# St1x.net
KiCad netlist of a schematic drawn in Altium Designer
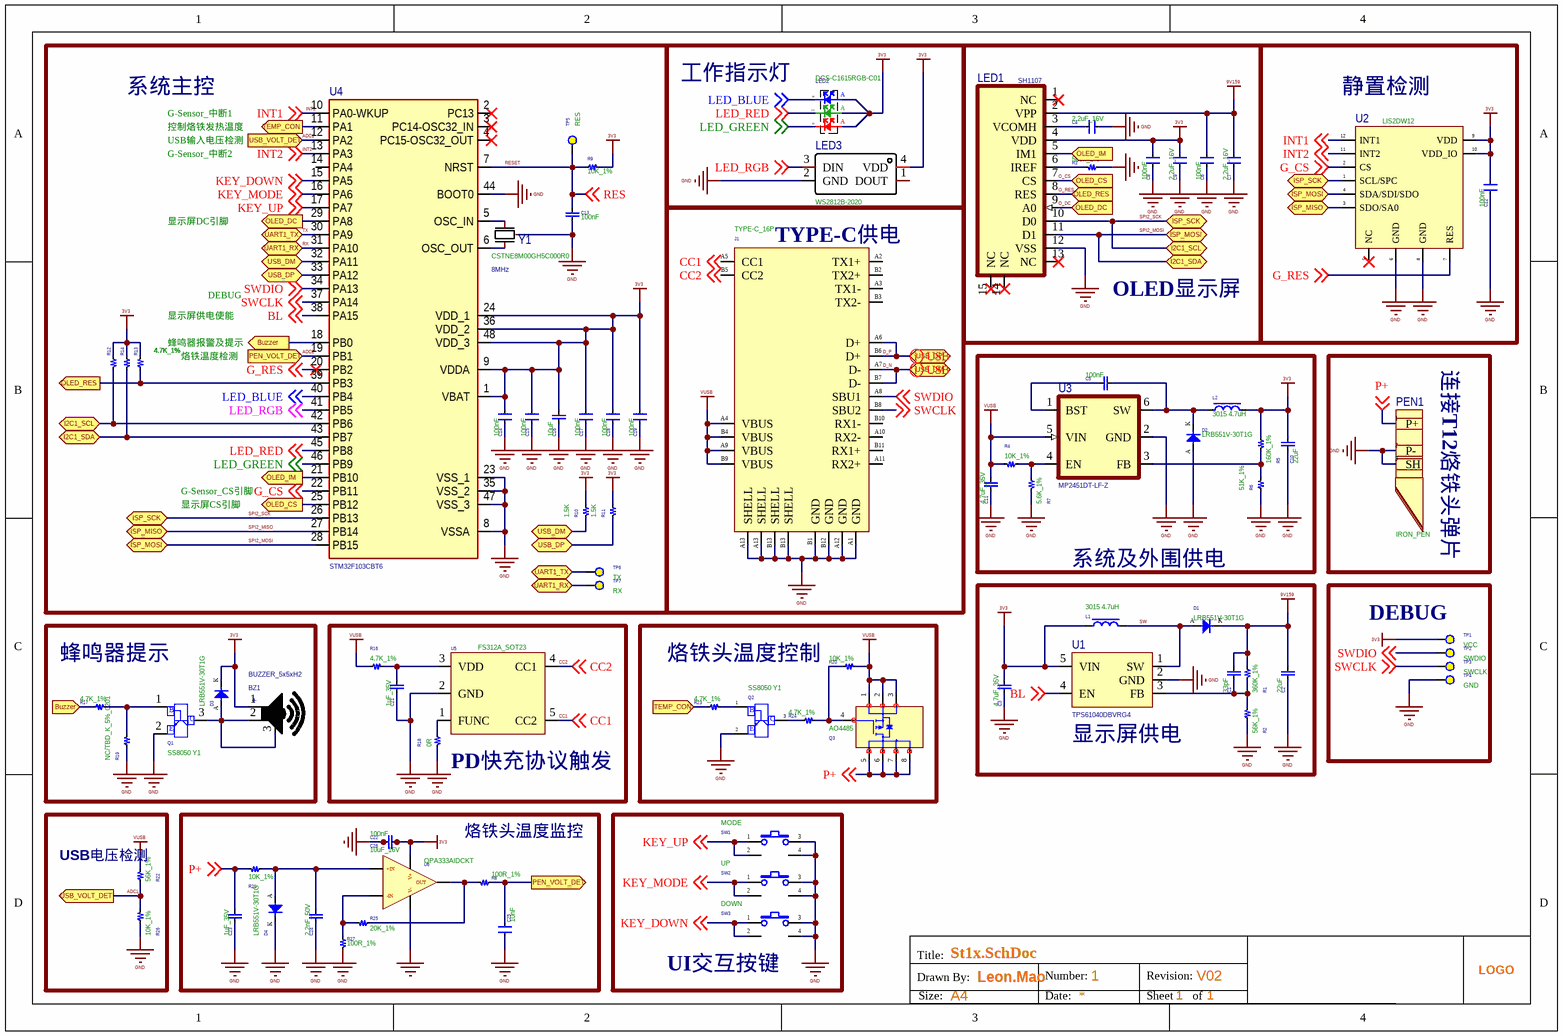
[diagram p0: St1x.SchDoc]

(export (version "E")
  (design (tool "Eeschema 10.0.6"))
  (components
    (comp (ref "BZ1")
      (value "BUZZER_5x5xH2")
      (footprint "BUZ-SMD_GSC5025YA")
      (description "电磁无源蜂鸣器(外部驱动)")
      (libsource (lib "SCHLIB_2022") (part "BZ"))
    )
    (comp (ref "C1")
      (value "33pF")
      (footprint "C1U0402")
      (description "贴片电容")
      (libsource (lib "SCHLIB_2022") (part "CAP_NP"))
    )
    (comp (ref "C2")
      (value "22uF")
      (footprint "CL0603")
      (description "贴片电容")
      (libsource (lib "SCHLIB_2022") (part "CAP_NP"))
    )
    (comp (ref "C3")
      (value "4.7uF_35V")
      (footprint "C4U0402")
      (description "贴片电容")
      (libsource (lib "SCHLIB_2022") (part "CAP_NP"))
    )
    (comp (ref "C4")
      (value "2.2uF_16V")
      (footprint "C4U0402")
      (description "贴片电容")
      (libsource (lib "") (part "CAP_NP_1"))
    )
    (comp (ref "C5")
      (value "100nF")
      (footprint "C1U0402")
      (description "贴片电容")
      (libsource (lib "SCHLIB_2022") (part "CAP_NP"))
    )
    (comp (ref "C6")
      (value "100nF")
      (footprint "C1U0402")
      (description "贴片电容")
      (libsource (lib "") (part "CAP_NP_1"))
    )
    (comp (ref "C7")
      (value "2.2uF_16V")
      (footprint "C4U0402")
      (description "贴片电容")
      (libsource (lib "") (part "CAP_NP_1"))
    )
    (comp (ref "C8")
      (value "100nF")
      (footprint "C1U0402")
      (description "贴片电容")
      (libsource (lib "") (part "CAP_NP_1"))
    )
    (comp (ref "C9")
      (value "2.2uF_16V")
      (footprint "C4U0402")
      (description "贴片电容")
      (libsource (lib "") (part "CAP_NP_1"))
    )
    (comp (ref "C10")
      (value "22uF")
      (footprint "CL0603")
      (description "贴片电容")
      (libsource (lib "SCHLIB_2022") (part "CAP_NP"))
    )
    (comp (ref "C11")
      (value "4.7uF_35V")
      (footprint "C4U0402")
      (description "贴片电容")
      (libsource (lib "SCHLIB_2022") (part "CAP_NP"))
    )
    (comp (ref "C12")
      (value "100nF")
      (footprint "C1U0402")
      (description "贴片电容")
      (libsource (lib "") (part "CAP_NP_1"))
    )
    (comp (ref "C13")
      (value "100nF")
      (footprint "C1U0402")
      (description "贴片电容")
      (libsource (lib "SCHLIB_2022") (part "CAP_NP"))
    )
    (comp (ref "C14")
      (value "100nF")
      (footprint "C1U0402")
      (description "贴片电容")
      (libsource (lib "") (part "CAP_NP_1"))
    )
    (comp (ref "C15")
      (value "100nF")
      (footprint "C1U0402")
      (description "贴片电容")
      (libsource (lib "") (part "CAP_NP_1"))
    )
    (comp (ref "C16")
      (value "10uF")
      (footprint "C4U0402")
      (description "贴片电容")
      (libsource (lib "SCHLIB_2022") (part "CAP_NP"))
    )
    (comp (ref "C17")
      (value "100nF")
      (footprint "C1U0402")
      (description "贴片电容")
      (libsource (lib "") (part "CAP_NP_1"))
    )
    (comp (ref "C18")
      (value "100nF")
      (footprint "C1U0402")
      (description "贴片电容")
      (libsource (lib "") (part "CAP_NP_1"))
    )
    (comp (ref "C19")
      (value "100nF")
      (footprint "C1U0402")
      (description "贴片电容")
      (libsource (lib "") (part "CAP_NP_1"))
    )
    (comp (ref "C21")
      (value "1uF_35V")
      (footprint "C1U0402")
      (description "贴片电容")
      (libsource (lib "SCHLIB_2022") (part "CAP_NP"))
    )
    (comp (ref "C22")
      (value "100nF")
      (footprint "C1U0402")
      (description "贴片电容")
      (libsource (lib "SCHLIB_2022") (part "CAP_NP"))
    )
    (comp (ref "C23")
      (value "1uF_35V")
      (footprint "C1U0402")
      (description "贴片电容")
      (libsource (lib "SCHLIB_2022") (part "CAP_NP"))
    )
    (comp (ref "C24")
      (value "2.2nF_50V")
      (footprint "C4U0402")
      (description "贴片电容")
      (libsource (lib "SCHLIB_2022") (part "CAP_NP"))
    )
    (comp (ref "C25")
      (value "10nF")
      (footprint "C1U0402")
      (description "贴片电容")
      (libsource (lib "") (part "CAP_NP_1"))
    )
    (comp (ref "C26")
      (value "10uF_16V")
      (footprint "C4U0402")
      (description "贴片电容")
      (libsource (lib "SCHLIB_2022") (part "CAP_NP"))
    )
    (comp (ref "D1")
      (value "LRB551V-30T1G")
      (footprint "SOD-323_AK")
      (description "肖特基二极管")
      (libsource (lib "Leon") (part "DIODE"))
    )
    (comp (ref "D2")
      (value "LRB551V-30T1G")
      (footprint "SOD-323_AK")
      (description "肖特基二极管")
      (libsource (lib "Leon") (part "DIODE"))
    )
    (comp (ref "D3")
      (value "LRB551V-30T1G")
      (footprint "SOD-323_AK")
      (description "肖特基二极管")
      (libsource (lib "Leon") (part "DIODE"))
    )
    (comp (ref "D4")
      (value "LRB551V-30T1G")
      (footprint "SOD-323_AK")
      (description "肖特基二极管")
      (libsource (lib "Leon") (part "DIODE"))
    )
    (comp (ref "J1")
      (value "TYPE-C_16P")
      (footprint "TYPE-C_16P")
      (description "TYPE-C母座")
      (libsource (lib "Leon") (part "TYPE-C_RI"))
    )
    (comp (ref "L1")
      (value "3015 4.7uH")
      (footprint "INDC3015")
      (description "功率电感")
      (libsource (lib "") (part "INDUCTOR_2_1"))
    )
    (comp (ref "L2")
      (value "3015 4.7uH")
      (footprint "INDC3015")
      (description "功率电感")
      (libsource (lib "SCHLIB_2022") (part "INDUCTOR_2"))
    )
    (comp (ref "LED1")
      (value "SH1107")
      (footprint "CON_13P_0.7mm-FPC")
      (description "QG-2880TSWKG01")
      (fields
        (field (name "MF") "{'manufacturer': u'Texas Instruments'}")
        (field (name "MP") "LP2985AIM5-5.0")
      )
      (libsource (lib "SCHLIB_2022") (part "SH1107"))
    )
    (comp (ref "LED2")
      (value "DCS-C1615RGB-C01")
      (footprint "RGB_DCS-C1615RGB-C01")
      (description "红绿蓝三色发光二极管")
      (libsource (lib "Leon") (part "LED_RGBS"))
    )
    (comp (ref "LED3")
      (value "WS2812B-2020")
      (footprint "LED_2020")
      (fields (field (name "MANUFACTURER PART") "Yo-WS2812B-3528反贴雾状"))
      (libsource (lib "altium-import") (part "root_0_mirrored_YO-WS2812B-3528反贴_"))
    )
    (comp (ref "PEN1") (value "IRON_PEN") (footprint "T13") (libsource (lib "SCHLIB_2022") (part "IRON_PEN")))
    (comp (ref "Q1")
      (value "SS8050 Y1")
      (footprint "SOT-23_123")
      (description "NPN三极管")
      (libsource (lib "PCBDEV_Library") (part "NPN"))
    )
    (comp (ref "Q2")
      (value "SS8050 Y1")
      (footprint "SOT-23_123")
      (description "NPN三极管")
      (libsource (lib "SCHLIB_2022") (part "NPN"))
    )
    (comp (ref "Q3")
      (value "AO4485")
      (footprint "SO-8M")
      (description "P沟道 40V 10A")
      (libsource (lib "SCHLIB_2022") (part "AO4485"))
    )
    (comp (ref "R1")
      (value "360K_1%")
      (footprint "RN0402")
      (description "贴片电阻")
      (libsource (lib "Leon") (part "ResSemi_3"))
    )
    (comp (ref "R2")
      (value "56K_1%")
      (footprint "RN0402")
      (description "贴片电阻")
      (libsource (lib "Leon") (part "ResSemi_3"))
    )
    (comp (ref "R3")
      (value "560k_1%")
      (footprint "RN0402")
      (description "贴片电阻")
      (libsource (lib "Leon") (part "ResSemi_3"))
    )
    (comp (ref "R4")
      (value "10K_1%")
      (footprint "RN0402")
      (description "贴片电阻")
      (libsource (lib "Leon") (part "ResSemi_3"))
    )
    (comp (ref "R5")
      (value "160K_1%")
      (footprint "RN0402")
      (description "贴片电阻")
      (libsource (lib "Leon") (part "ResSemi_3"))
    )
    (comp (ref "R6")
      (value "51K_1%")
      (footprint "RN0402")
      (description "贴片电阻")
      (libsource (lib "Leon") (part "ResSemi_3"))
    )
    (comp (ref "R7")
      (value "5.6K_1%")
      (footprint "RN0402")
      (description "贴片电阻")
      (libsource (lib "Leon") (part "ResSemi_3"))
    )
    (comp (ref "R8")
      (value "100R_1%")
      (footprint "RN0402")
      (description "贴片电阻")
      (libsource (lib "Leon") (part "ResSemi_3"))
    )
    (comp (ref "R9")
      (value "10K_1%")
      (footprint "RN0402")
      (description "贴片电阻")
      (libsource (lib "Leon") (part "ResSemi_3"))
    )
    (comp (ref "R10")
      (value "1.5K")
      (footprint "RN0402")
      (description "贴片电阻")
      (libsource (lib "Leon") (part "ResSemi_3"))
    )
    (comp (ref "R11")
      (value "1.5K")
      (footprint "RN0402")
      (description "贴片电阻")
      (libsource (lib "Leon") (part "ResSemi_3"))
    )
    (comp (ref "R12")
      (value "4.7K_1%")
      (footprint "RN0402")
      (description "贴片电阻")
      (libsource (lib "Leon") (part "ResSemi_3"))
    )
    (comp (ref "R13")
      (value "4.7K_1%")
      (footprint "RN0402")
      (description "贴片电阻")
      (libsource (lib "Leon") (part "ResSemi_3"))
    )
    (comp (ref "R14")
      (value "4.7K_1%")
      (footprint "RN0402")
      (description "贴片电阻")
      (libsource (lib "Leon") (part "ResSemi_3"))
    )
    (comp (ref "R16")
      (value "4.7K_1%")
      (footprint "RN0402")
      (description "贴片电阻")
      (libsource (lib "Leon") (part "ResSemi_3"))
    )
    (comp (ref "R17")
      (value "4.7K_1%")
      (footprint "RN0402")
      (description "贴片电阻")
      (libsource (lib "Leon") (part "ResSemi_3"))
    )
    (comp (ref "R18")
      (value "0R")
      (footprint "RN0402")
      (description "贴片电阻")
      (libsource (lib "Leon") (part "ResSemi_3"))
    )
    (comp (ref "R19")
      (value "NC/TBD_K_5%_0201")
      (footprint "RN0402")
      (description "贴片电阻")
      (libsource (lib "Leon") (part "ResSemi_3"))
    )
    (comp (ref "R20")
      (value "10K_1%")
      (footprint "RN0402")
      (description "贴片电阻")
      (libsource (lib "Leon") (part "ResSemi_3"))
    )
    (comp (ref "R21")
      (value "10K_1%")
      (footprint "RN0603")
      (description "贴片电阻")
      (libsource (lib "Leon") (part "ResSemi_3"))
    )
    (comp (ref "R22")
      (value "56K_1%")
      (footprint "RN0402")
      (description "贴片电阻")
      (libsource (lib "Leon") (part "ResSemi_3"))
    )
    (comp (ref "R23")
      (value "4.7K_1%")
      (footprint "RN0402")
      (description "贴片电阻")
      (libsource (lib "Leon") (part "ResSemi_3"))
    )
    (comp (ref "R24")
      (value "4.7K_1%")
      (footprint "RN0402")
      (description "贴片电阻")
      (libsource (lib "Leon") (part "ResSemi_3"))
    )
    (comp (ref "R25")
      (value "20K_1%")
      (footprint "RN0402")
      (description "贴片电阻")
      (libsource (lib "Leon") (part "ResSemi_3"))
    )
    (comp (ref "R26")
      (value "10K_1%")
      (footprint "RN0402")
      (description "贴片电阻")
      (libsource (lib "Leon") (part "ResSemi_3"))
    )
    (comp (ref "R27")
      (value "100R_1%")
      (footprint "RN0402")
      (description "贴片电阻")
      (libsource (lib "Leon") (part "ResSemi_3"))
    )
    (comp (ref "SW1")
      (value "MODE")
      (footprint "KEY-SMD_4P-L4.2-W3.2-P2.20-LS5.1-TL")
      (description "轻触开关")
      (libsource (lib "SCHLIB_2022") (part "SW PUSHBUTTON"))
    )
    (comp (ref "SW2")
      (value "UP")
      (footprint "KEY-SMD_4P-L4.2-W3.2-P2.20-LS5.1-TL")
      (description "轻触开关")
      (libsource (lib "SCHLIB_2022") (part "SW PUSHBUTTON"))
    )
    (comp (ref "SW3")
      (value "DOWN")
      (footprint "KEY-SMD_4P-L4.2-W3.2-P2.20-LS5.1-TL")
      (description "轻触开关")
      (libsource (lib "SCHLIB_2022") (part "SW PUSHBUTTON"))
    )
    (comp (ref "TP1") (value "VCC") (footprint "SMD0808") (libsource (lib "SCHLIB_2022") (part "TEST")))
    (comp (ref "TP2") (value "SWDIO") (footprint "SMD0808") (libsource (lib "SCHLIB_2022") (part "TEST")))
    (comp (ref "TP3") (value "SWCLK") (footprint "SMD0808") (libsource (lib "SCHLIB_2022") (part "TEST")))
    (comp (ref "TP4") (value "GND") (footprint "SMD0808") (libsource (lib "SCHLIB_2022") (part "TEST")))
    (comp (ref "TP5") (value "RES") (footprint "SMD0808") (libsource (lib "SCHLIB_2022") (part "TEST")))
    (comp (ref "TP6") (value "TX") (footprint "SMD0808") (libsource (lib "SCHLIB_2022") (part "TEST")))
    (comp (ref "TP7") (value "RX") (footprint "SMD0808") (libsource (lib "SCHLIB_2022") (part "TEST")))
    (comp (ref "U1")
      (value "TPS61040DBVRG4")
      (footprint "SOT23-5")
      (description "DC-DC芯片")
      (libsource (lib "SCHLIB_2022") (part "TPS61040DBVRG4_[C7722]"))
    )
    (comp (ref "U2")
      (value "LIS2DW12")
      (footprint "LGA12_20x20x07")
      (libsource (lib "SCHLIB_2022") (part "LIS2DW12"))
    )
    (comp (ref "U3")
      (value "MP2451DT-LF-Z")
      (footprint "SOT23-6")
      (fields
        (field (name "MF") "{'manufacturer': u'Texas Instruments'}")
        (field (name "MP") "LP2985AIM5-5.0")
      )
      (libsource (lib "SCHLIB_2022") (part "MP2451DT-LF-Z"))
    )
    (comp (ref "U4")
      (value "STM32F103CBT6")
      (footprint "LQFP48-7x7mm")
      (description "No Description Available")
      (fields (field (name "COPYRIGHT") "Copyright (C) 2023 Ultra Librarian. All rights reserved."))
      (libsource (lib "SCHLIB_2022") (part "STM32F103CBT6"))
    )
    (comp (ref "U5")
      (value "FS312A_SOT23")
      (footprint "SOT23-5")
      (description "USB Type-C PD快充协议智能触发芯片")
      (libsource (lib "SCHLIB_2022") (part "FS312A"))
    )
    (comp (ref "U6")
      (value "OPA333AIDCKT")
      (footprint "SOT23-5")
      (libsource (lib "SCHLIB_2022") (part "OPA333_SOT23"))
    )
    (comp (ref "Y1")
      (value "CSTNE8M00GH5C000R0")
      (footprint "OSC-SMD_3P-L3.2-W1.3-P1.20-L")
      (description "频率:8MHz;频率容差:±0.07%;内藏负载电容:33pF;谐振阻抗:40Ω;")
      (fields (field (name "MANUFACTURER") "muRata(村田)") (field (name "ALTIUM_VALUE") "8MHz"))
      (libsource (lib "SCHLIB_2022") (part "CSTNE8M00GH5C000R0"))
    )
  )
  (nets
    (net (code "1") (name "/ADC1") (class "Default")
      (node (ref "R22") (pin "1") (pinfunction "1_1") (pintype "passive"))
      (node (ref "R26") (pin "2") (pinfunction "2_2") (pintype "passive"))
      (node (ref "U4") (pin "12") (pinfunction "PA2_12") (pintype "passive"))
    )
    (net (code "2") (name "/ADC2") (class "Default")
      (node (ref "C25") (pin "1") (pinfunction "1_1") (pintype "passive"))
      (node (ref "R8") (pin "1") (pinfunction "1_1") (pintype "passive"))
      (node (ref "U4") (pin "19") (pinfunction "PB1_19") (pintype "passive"))
    )
    (net (code "3") (name "/Buzzer") (class "Default")
      (node (ref "R17") (pin "1") (pinfunction "1_1") (pintype "passive"))
      (node (ref "U4") (pin "18") (pinfunction "PB0_18") (pintype "passive"))
    )
    (net (code "4") (name "/D_N") (class "Default")
      (node (ref "J1") (pin "A7") (pinfunction "D-_A7") (pintype "passive"))
      (node (ref "J1") (pin "B7") (pinfunction "D-_B7") (pintype "passive"))
      (node (ref "R10") (pin "2") (pinfunction "2_2") (pintype "passive"))
      (node (ref "U4") (pin "32") (pinfunction "PA11_32") (pintype "passive"))
    )
    (net (code "5") (name "/D_P") (class "Default")
      (node (ref "J1") (pin "A6") (pinfunction "D+_A6") (pintype "passive"))
      (node (ref "J1") (pin "B6") (pinfunction "D+_B6") (pintype "passive"))
      (node (ref "R11") (pin "2") (pinfunction "2_2") (pintype "passive"))
      (node (ref "U4") (pin "33") (pinfunction "PA12_33") (pintype "passive"))
    )
    (net (code "6") (name "/OLED_IM") (class "Default")
      (node (ref "LED1") (pin "5") (pinfunction "IM1_5") (pintype "passive"))
      (node (ref "U4") (pin "21") (pinfunction "PB10_21") (pintype "passive"))
    )
    (net (code "7") (name "/O_CS") (class "Default")
      (node (ref "LED1") (pin "7") (pinfunction "CS_7") (pintype "passive"))
      (node (ref "U4") (pin "25") (pinfunction "PB12_25") (pintype "passive"))
    )
    (net (code "8") (name "/O_DC") (class "Default")
      (node (ref "LED1") (pin "9") (pinfunction "A0_9") (pintype "input"))
      (node (ref "U4") (pin "29") (pinfunction "PA8_29") (pintype "passive"))
    )
    (net (code "9") (name "/O_RES") (class "Default")
      (node (ref "LED1") (pin "8") (pinfunction "RES_8") (pintype "passive"))
      (node (ref "R13") (pin "2") (pinfunction "2_2") (pintype "passive"))
      (node (ref "U4") (pin "39") (pinfunction "PB3_39") (pintype "passive"))
    )
    (net (code "10") (name "/RX") (class "Default")
      (node (ref "TP7") (pin "1") (pinfunction "1_1") (pintype "passive"))
      (node (ref "U4") (pin "31") (pinfunction "PA10_31") (pintype "passive"))
    )
    (net (code "11") (name "/SPI2_MISO") (class "Default")
      (node (ref "U2") (pin "3") (pinfunction "SDO/SA0_3") (pintype "passive"))
      (node (ref "U4") (pin "27") (pinfunction "PB14_27") (pintype "passive"))
    )
    (net (code "12") (name "/SPI2_MOSI") (class "Default")
      (node (ref "LED1") (pin "11") (pinfunction "D1_11") (pintype "passive"))
      (node (ref "R14") (pin "1") (pinfunction "1_1") (pintype "passive"))
      (node (ref "U2") (pin "4") (pinfunction "SDA/SDI/SDO_4") (pintype "passive"))
      (node (ref "U4") (pin "28") (pinfunction "PB15_28") (pintype "passive"))
      (node (ref "U4") (pin "43") (pinfunction "PB7_43") (pintype "passive"))
    )
    (net (code "13") (name "/SPI2_SCK") (class "Default")
      (node (ref "LED1") (pin "10") (pinfunction "D0_10") (pintype "passive"))
      (node (ref "R12") (pin "1") (pinfunction "1_1") (pintype "passive"))
      (node (ref "U2") (pin "1") (pinfunction "SCL/SPC_1") (pintype "passive"))
      (node (ref "U4") (pin "26") (pinfunction "PB13_26") (pintype "passive"))
      (node (ref "U4") (pin "42") (pinfunction "PB6_42") (pintype "passive"))
    )
    (net (code "14") (name "/SW") (class "Default")
      (node (ref "D1") (pin "A") (pinfunction "ANODE_A") (pintype "passive"))
      (node (ref "L1") (pin "2") (pinfunction "2_2") (pintype "passive"))
      (node (ref "U1") (pin "1") (pinfunction "SW_1") (pintype "passive"))
    )
    (net (code "15") (name "/TEMP_CON") (class "Default")
      (node (ref "R23") (pin "1") (pinfunction "1_1") (pintype "passive"))
      (node (ref "U4") (pin "11") (pinfunction "PA1_11") (pintype "passive"))
    )
    (net (code "16") (name "/TX") (class "Default")
      (node (ref "TP6") (pin "1") (pinfunction "1_1") (pintype "passive"))
      (node (ref "U4") (pin "30") (pinfunction "PA9_30") (pintype "passive"))
    )
    (net (code "17") (name "3V3") (class "Default")
      (node (ref "BZ1") (pin "1") (pinfunction "+_1") (pintype "passive"))
      (node (ref "C10") (pin "2") (pinfunction "2_2") (pintype "passive"))
      (node (ref "C12") (pin "1") (pinfunction "1_1") (pintype "passive"))
      (node (ref "C14") (pin "1") (pinfunction "1_1") (pintype "passive"))
      (node (ref "C15") (pin "1") (pinfunction "1_1") (pintype "passive"))
      (node (ref "C16") (pin "2") (pinfunction "2_2") (pintype "passive"))
      (node (ref "C17") (pin "1") (pinfunction "1_1") (pintype "passive"))
      (node (ref "C18") (pin "1") (pinfunction "1_1") (pintype "passive"))
      (node (ref "C19") (pin "1") (pinfunction "1_1") (pintype "passive"))
      (node (ref "C22") (pin "2") (pinfunction "2_2") (pintype "passive"))
      (node (ref "C26") (pin "1") (pinfunction "1_1") (pintype "passive"))
      (node (ref "C3") (pin "2") (pinfunction "2_2") (pintype "passive"))
      (node (ref "C8") (pin "1") (pinfunction "1_1") (pintype "passive"))
      (node (ref "C9") (pin "1") (pinfunction "1_1") (pintype "passive"))
      (node (ref "D3") (pin "K") (pinfunction "CATHODE_K") (pintype "passive"))
      (node (ref "L1") (pin "1") (pinfunction "1_1") (pintype "passive"))
      (node (ref "L2") (pin "1") (pinfunction "1_1") (pintype "passive"))
      (node (ref "LED1") (pin "4") (pinfunction "VDD_4") (pintype "power_in"))
      (node (ref "LED2") (pin "A") (pinfunction "A_A") (pintype "passive"))
      (node (ref "LED3") (pin "4") (pinfunction "VDD_4") (pintype "passive"))
      (node (ref "R10") (pin "1") (pinfunction "1_1") (pintype "passive"))
      (node (ref "R11") (pin "1") (pinfunction "1_1") (pintype "passive"))
      (node (ref "R12") (pin "2") (pinfunction "2_2") (pintype "passive"))
      (node (ref "R13") (pin "1") (pinfunction "1_1") (pintype "passive"))
      (node (ref "R14") (pin "2") (pinfunction "2_2") (pintype "passive"))
      (node (ref "R5") (pin "1") (pinfunction "1_1") (pintype "passive"))
      (node (ref "R9") (pin "1") (pinfunction "1_1") (pintype "passive"))
      (node (ref "TP1") (pin "1") (pinfunction "1_1") (pintype "passive"))
      (node (ref "U1") (pin "5") (pinfunction "VIN_5") (pintype "passive"))
      (node (ref "U2") (pin "10") (pinfunction "VDD_IO_10") (pintype "passive"))
      (node (ref "U2") (pin "9") (pinfunction "VDD_9") (pintype "passive"))
      (node (ref "U4") (pin "1") (pinfunction "VBAT_1") (pintype "power_in"))
      (node (ref "U4") (pin "24") (pinfunction "VDD_1_24") (pintype "power_in"))
      (node (ref "U4") (pin "36") (pinfunction "VDD_2_36") (pintype "power_in"))
      (node (ref "U4") (pin "48") (pinfunction "VDD_3_48") (pintype "power_in"))
      (node (ref "U4") (pin "9") (pinfunction "VDDA_9") (pintype "power_in"))
      (node (ref "U6") (pin "5") (pinfunction "V+_5") (pintype "passive"))
    )
    (net (code "18") (name "9V159") (class "Default")
      (node (ref "C1") (pin "2") (pinfunction "2_2") (pintype "passive"))
      (node (ref "C2") (pin "2") (pinfunction "2_2") (pintype "passive"))
      (node (ref "C6") (pin "1") (pinfunction "1_1") (pintype "passive"))
      (node (ref "C7") (pin "1") (pinfunction "1_1") (pintype "passive"))
      (node (ref "D1") (pin "K") (pinfunction "CATHODE_K") (pintype "passive"))
      (node (ref "LED1") (pin "2") (pinfunction "VPP_2") (pintype "power_in"))
      (node (ref "R1") (pin "1") (pinfunction "1_1") (pintype "passive"))
    )
    (net (code "19") (name "BL") (class "Default")
      (node (ref "U1") (pin "4") (pinfunction "EN_4") (pintype "passive"))
      (node (ref "U4") (pin "38") (pinfunction "PA15_38") (pintype "passive"))
    )
    (net (code "20") (name "CC1") (class "Default")
      (node (ref "J1") (pin "A5") (pinfunction "CC1_A5") (pintype "passive"))
      (node (ref "U5") (pin "5") (pinfunction "CC2_5") (pintype "passive"))
    )
    (net (code "21") (name "CC2") (class "Default")
      (node (ref "J1") (pin "B5") (pinfunction "CC2_B5") (pintype "passive"))
      (node (ref "U5") (pin "4") (pinfunction "CC1_4") (pintype "passive"))
    )
    (net (code "22") (name "GND") (class "Default")
      (node (ref "C10") (pin "1") (pinfunction "1_1") (pintype "passive"))
      (node (ref "C11") (pin "1") (pinfunction "1_1") (pintype "passive"))
      (node (ref "C12") (pin "2") (pinfunction "2_2") (pintype "passive"))
      (node (ref "C13") (pin "2") (pinfunction "2_2") (pintype "passive"))
      (node (ref "C14") (pin "2") (pinfunction "2_2") (pintype "passive"))
      (node (ref "C15") (pin "2") (pinfunction "2_2") (pintype "passive"))
      (node (ref "C16") (pin "1") (pinfunction "1_1") (pintype "passive"))
      (node (ref "C17") (pin "2") (pinfunction "2_2") (pintype "passive"))
      (node (ref "C18") (pin "2") (pinfunction "2_2") (pintype "passive"))
      (node (ref "C19") (pin "2") (pinfunction "2_2") (pintype "passive"))
      (node (ref "C2") (pin "1") (pinfunction "1_1") (pintype "passive"))
      (node (ref "C21") (pin "1") (pinfunction "1_1") (pintype "passive"))
      (node (ref "C22") (pin "1") (pinfunction "1_1") (pintype "passive"))
      (node (ref "C23") (pin "2") (pinfunction "2_2") (pintype "passive"))
      (node (ref "C24") (pin "2") (pinfunction "2_2") (pintype "passive"))
      (node (ref "C25") (pin "2") (pinfunction "2_2") (pintype "passive"))
      (node (ref "C26") (pin "2") (pinfunction "2_2") (pintype "passive"))
      (node (ref "C3") (pin "1") (pinfunction "1_1") (pintype "passive"))
      (node (ref "C4") (pin "2") (pinfunction "2_2") (pintype "passive"))
      (node (ref "C6") (pin "2") (pinfunction "2_2") (pintype "passive"))
      (node (ref "C7") (pin "2") (pinfunction "2_2") (pintype "passive"))
      (node (ref "C8") (pin "2") (pinfunction "2_2") (pintype "passive"))
      (node (ref "C9") (pin "2") (pinfunction "2_2") (pintype "passive"))
      (node (ref "D2") (pin "A") (pinfunction "ANODE_A") (pintype "passive"))
      (node (ref "D4") (pin "K") (pinfunction "CATHODE_K") (pintype "passive"))
      (node (ref "J1") (pin "A1") (pinfunction "GND_A1") (pintype "passive"))
      (node (ref "J1") (pin "A12") (pinfunction "GND_A12") (pintype "passive"))
      (node (ref "J1") (pin "A13") (pinfunction "SHELL_A13") (pintype "passive"))
      (node (ref "J1") (pin "B1") (pinfunction "GND_B1") (pintype "passive"))
      (node (ref "J1") (pin "B12") (pinfunction "GND_B12") (pintype "passive"))
      (node (ref "J1") (pin "B13") (pinfunction "SHELL_B13") (pintype "passive"))
      (node (ref "LED1") (pin "12") (pinfunction "VSS_12") (pintype "passive"))
      (node (ref "LED3") (pin "2") (pinfunction "GND_2") (pintype "passive"))
      (node (ref "PEN1") (pin "2") (pinfunction "P-_2") (pintype "passive"))
      (node (ref "PEN1") (pin "3") (pinfunction "SH_3") (pintype "passive"))
      (node (ref "Q1") (pin "2") (pinfunction "EMITTER_2") (pintype "passive"))
      (node (ref "Q2") (pin "2") (pinfunction "EMITTER_2") (pintype "passive"))
      (node (ref "R18") (pin "2") (pinfunction "2_2") (pintype "passive"))
      (node (ref "R19") (pin "1") (pinfunction "1_1") (pintype "passive"))
      (node (ref "R2") (pin "1") (pinfunction "1_1") (pintype "passive"))
      (node (ref "R26") (pin "1") (pinfunction "1_1") (pintype "passive"))
      (node (ref "R27") (pin "2") (pinfunction "2_2") (pintype "passive"))
      (node (ref "R3") (pin "1") (pinfunction "1_1") (pintype "passive"))
      (node (ref "R6") (pin "1") (pinfunction "1_1") (pintype "passive"))
      (node (ref "R7") (pin "2") (pinfunction "2_2") (pintype "passive"))
      (node (ref "SW1") (pin "3") (pinfunction "3_3") (pintype "passive"))
      (node (ref "SW1") (pin "4") (pinfunction "4_4") (pintype "passive"))
      (node (ref "SW2") (pin "3") (pinfunction "3_3") (pintype "passive"))
      (node (ref "SW2") (pin "4") (pinfunction "4_4") (pintype "passive"))
      (node (ref "SW3") (pin "3") (pinfunction "3_3") (pintype "passive"))
      (node (ref "SW3") (pin "4") (pinfunction "4_4") (pintype "passive"))
      (node (ref "TP4") (pin "1") (pinfunction "1_1") (pintype "passive"))
      (node (ref "U1") (pin "2") (pinfunction "GND_2") (pintype "passive"))
      (node (ref "U2") (pin "6") (pinfunction "GND_6") (pintype "passive"))
      (node (ref "U2") (pin "8") (pinfunction "GND_8") (pintype "passive"))
      (node (ref "U3") (pin "2") (pinfunction "GND_2") (pintype "power_in"))
      (node (ref "U4") (pin "23") (pinfunction "VSS_1_23") (pintype "power_in"))
      (node (ref "U4") (pin "35") (pinfunction "VSS_2_35") (pintype "power_in"))
      (node (ref "U4") (pin "44") (pinfunction "BOOT0_44") (pintype "passive"))
      (node (ref "U4") (pin "47") (pinfunction "VSS_3_47") (pintype "power_in"))
      (node (ref "U4") (pin "8") (pinfunction "VSSA_8") (pintype "power_in"))
      (node (ref "U5") (pin "2") (pinfunction "GND_2") (pintype "passive"))
      (node (ref "U6") (pin "2") (pinfunction "V-_2") (pintype "passive"))
      (node (ref "Y1") (pin "2") (pinfunction "GND_2") (pintype "passive"))
    )
    (net (code "23") (name "G_CS") (class "Default")
      (node (ref "U2") (pin "2") (pinfunction "CS_2") (pintype "passive"))
      (node (ref "U4") (pin "22") (pinfunction "PB11_22") (pintype "passive"))
    )
    (net (code "24") (name "G_RES") (class "Default")
      (node (ref "U2") (pin "7") (pinfunction "RES_7") (pintype "passive"))
      (node (ref "U4") (pin "20") (pinfunction "PB2_20") (pintype "passive"))
    )
    (net (code "25") (name "INT1") (class "Default")
      (node (ref "U2") (pin "12") (pinfunction "INT1_12") (pintype "passive"))
      (node (ref "U4") (pin "10") (pinfunction "PA0-WKUP_10") (pintype "passive"))
    )
    (net (code "26") (name "INT2") (class "Default")
      (node (ref "U2") (pin "11") (pinfunction "INT2_11") (pintype "passive"))
      (node (ref "U4") (pin "13") (pinfunction "PA3_13") (pintype "passive"))
    )
    (net (code "27") (name "KEY_DOWN") (class "Default")
      (node (ref "SW3") (pin "1") (pinfunction "1_1") (pintype "passive"))
      (node (ref "SW3") (pin "2") (pinfunction "2_2") (pintype "passive"))
      (node (ref "U4") (pin "15") (pinfunction "PA5_15") (pintype "passive"))
    )
    (net (code "28") (name "KEY_MODE") (class "Default")
      (node (ref "SW2") (pin "1") (pinfunction "1_1") (pintype "passive"))
      (node (ref "SW2") (pin "2") (pinfunction "2_2") (pintype "passive"))
      (node (ref "U4") (pin "16") (pinfunction "PA6_16") (pintype "passive"))
    )
    (net (code "29") (name "KEY_UP") (class "Default")
      (node (ref "SW1") (pin "1") (pinfunction "1_1") (pintype "passive"))
      (node (ref "SW1") (pin "2") (pinfunction "2_2") (pintype "passive"))
      (node (ref "U4") (pin "17") (pinfunction "PA7_17") (pintype "passive"))
    )
    (net (code "30") (name "LED_BLUE") (class "Default")
      (node (ref "LED2") (pin "BC") (pinfunction "BC_BC") (pintype "passive"))
      (node (ref "U4") (pin "40") (pinfunction "PB4_40") (pintype "passive"))
    )
    (net (code "31") (name "LED_GREEN") (class "Default")
      (node (ref "LED2") (pin "RC") (pinfunction "RC_RC") (pintype "passive"))
      (node (ref "U4") (pin "46") (pinfunction "PB9_46") (pintype "passive"))
    )
    (net (code "32") (name "LED_RED") (class "Default")
      (node (ref "LED2") (pin "GC") (pinfunction "GC_GC") (pintype "passive"))
      (node (ref "U4") (pin "45") (pinfunction "PB8_45") (pintype "passive"))
    )
    (net (code "33") (name "LED_RGB") (class "Default")
      (node (ref "LED3") (pin "3") (pinfunction "DIN_3") (pintype "passive"))
      (node (ref "U4") (pin "41") (pinfunction "PB5_41") (pintype "passive"))
    )
    (net (code "34") (name "Net-(D2-CATHODE)") (class "Default")
      (node (ref "C5") (pin "1") (pinfunction "1_1") (pintype "passive"))
      (node (ref "D2") (pin "K") (pinfunction "CATHODE_K") (pintype "passive"))
      (node (ref "L2") (pin "2") (pinfunction "2_2") (pintype "passive"))
      (node (ref "U3") (pin "6") (pinfunction "SW_6") (pintype "passive"))
    )
    (net (code "35") (name "Net-(D3-ANODE)") (class "Default")
      (node (ref "BZ1") (pin "2") (pinfunction "-_2") (pintype "passive"))
      (node (ref "BZ1") (pin "3") (pinfunction "-_3") (pintype "passive"))
      (node (ref "D3") (pin "A") (pinfunction "ANODE_A") (pintype "passive"))
      (node (ref "Q1") (pin "3") (pinfunction "COLLECTOR_3") (pintype "passive"))
    )
    (net (code "36") (name "Net-(D4-ANODE)") (class "Default")
      (node (ref "C24") (pin "1") (pinfunction "1_1") (pintype "passive"))
      (node (ref "D4") (pin "A") (pinfunction "ANODE_A") (pintype "passive"))
      (node (ref "R21") (pin "1") (pinfunction "1_1") (pintype "passive"))
      (node (ref "U6") (pin "3") (pinfunction "+IN_3") (pintype "passive"))
    )
    (net (code "37") (name "Net-(LED1-IREF)") (class "Default")
      (node (ref "LED1") (pin "6") (pinfunction "IREF_6") (pintype "passive"))
      (node (ref "R3") (pin "2") (pinfunction "2_2") (pintype "passive"))
    )
    (net (code "38") (name "Net-(LED1-VCOMH)") (class "Default")
      (node (ref "C4") (pin "1") (pinfunction "1_1") (pintype "passive"))
      (node (ref "LED1") (pin "3") (pinfunction "VCOMH_3") (pintype "passive"))
    )
    (net (code "39") (name "Net-(Q1-BASE)") (class "Default")
      (node (ref "Q1") (pin "1") (pinfunction "BASE_1") (pintype "passive"))
      (node (ref "R17") (pin "2") (pinfunction "2_2") (pintype "passive"))
      (node (ref "R19") (pin "2") (pinfunction "2_2") (pintype "passive"))
    )
    (net (code "40") (name "Net-(Q2-BASE)") (class "Default")
      (node (ref "Q2") (pin "1") (pinfunction "BASE_1") (pintype "passive"))
      (node (ref "R23") (pin "2") (pinfunction "2_2") (pintype "passive"))
    )
    (net (code "41") (name "Net-(Q2-COLLECTOR)") (class "Default")
      (node (ref "Q2") (pin "3") (pinfunction "COLLECTOR_3") (pintype "passive"))
      (node (ref "R24") (pin "1") (pinfunction "1_1") (pintype "passive"))
    )
    (net (code "42") (name "Net-(Q3-G)") (class "Default")
      (node (ref "Q3") (pin "4") (pinfunction "G_4") (pintype "passive"))
      (node (ref "R20") (pin "1") (pinfunction "1_1") (pintype "passive"))
      (node (ref "R24") (pin "2") (pinfunction "2_2") (pintype "passive"))
    )
    (net (code "43") (name "Net-(U1-FB)") (class "Default")
      (node (ref "C1") (pin "1") (pinfunction "1_1") (pintype "passive"))
      (node (ref "R1") (pin "2") (pinfunction "2_2") (pintype "passive"))
      (node (ref "R2") (pin "2") (pinfunction "2_2") (pintype "passive"))
      (node (ref "U1") (pin "3") (pinfunction "FB_3") (pintype "passive"))
    )
    (net (code "44") (name "Net-(U3-BST)") (class "Default")
      (node (ref "C5") (pin "2") (pinfunction "2_2") (pintype "passive"))
      (node (ref "U3") (pin "1") (pinfunction "BST_1") (pintype "passive"))
    )
    (net (code "45") (name "Net-(U3-EN)") (class "Default")
      (node (ref "R4") (pin "1") (pinfunction "1_1") (pintype "passive"))
      (node (ref "R7") (pin "1") (pinfunction "1_1") (pintype "passive"))
      (node (ref "U3") (pin "4") (pinfunction "EN_4") (pintype "passive"))
    )
    (net (code "46") (name "Net-(U3-FB)") (class "Default")
      (node (ref "R5") (pin "2") (pinfunction "2_2") (pintype "passive"))
      (node (ref "R6") (pin "2") (pinfunction "2_2") (pintype "passive"))
      (node (ref "U3") (pin "3") (pinfunction "FB_3") (pintype "passive"))
    )
    (net (code "47") (name "Net-(U4-OSC_IN)") (class "Default")
      (node (ref "U4") (pin "5") (pinfunction "OSC_IN_5") (pintype "passive"))
      (node (ref "Y1") (pin "1") (pinfunction "OSC1_1") (pintype "passive"))
    )
    (net (code "48") (name "Net-(U4-OSC_OUT)") (class "Default")
      (node (ref "U4") (pin "6") (pinfunction "OSC_OUT_6") (pintype "passive"))
      (node (ref "Y1") (pin "3") (pinfunction "OSC2_3") (pintype "passive"))
    )
    (net (code "49") (name "Net-(U5-FUNC)") (class "Default")
      (node (ref "R18") (pin "1") (pinfunction "1_1") (pintype "passive"))
      (node (ref "U5") (pin "1") (pinfunction "FUNC_1") (pintype "passive"))
    )
    (net (code "50") (name "Net-(U5-VDD)") (class "Default")
      (node (ref "C21") (pin "2") (pinfunction "2_2") (pintype "passive"))
      (node (ref "R16") (pin "2") (pinfunction "2_2") (pintype "passive"))
      (node (ref "U5") (pin "3") (pinfunction "VDD_3") (pintype "passive"))
    )
    (net (code "51") (name "Net-(U6--IN)") (class "Default")
      (node (ref "R25") (pin "2") (pinfunction "2_2") (pintype "passive"))
      (node (ref "R27") (pin "1") (pinfunction "1_1") (pintype "passive"))
      (node (ref "U6") (pin "4") (pinfunction "-IN_4") (pintype "passive"))
    )
    (net (code "52") (name "Net-(U6-OUT)") (class "Default")
      (node (ref "R25") (pin "1") (pinfunction "1_1") (pintype "passive"))
      (node (ref "R8") (pin "2") (pinfunction "2_2") (pintype "passive"))
      (node (ref "U6") (pin "1") (pinfunction "OUT_1") (pintype "passive"))
    )
    (net (code "53") (name "P+") (class "Default")
      (node (ref "C23") (pin "1") (pinfunction "1_1") (pintype "passive"))
      (node (ref "PEN1") (pin "1") (pinfunction "P+_1") (pintype "passive"))
      (node (ref "Q3") (pin "5") (pinfunction "D_5") (pintype "passive"))
      (node (ref "Q3") (pin "6") (pinfunction "D_6") (pintype "passive"))
      (node (ref "Q3") (pin "7") (pinfunction "D_7") (pintype "passive"))
      (node (ref "Q3") (pin "8") (pinfunction "D_8") (pintype "passive"))
      (node (ref "R21") (pin "2") (pinfunction "2_2") (pintype "passive"))
    )
    (net (code "54") (name "RES") (class "Default")
      (node (ref "C13") (pin "1") (pinfunction "1_1") (pintype "passive"))
      (node (ref "R9") (pin "2") (pinfunction "2_2") (pintype "passive"))
      (node (ref "TP5") (pin "1") (pinfunction "1_1") (pintype "passive"))
      (node (ref "U4") (pin "7") (pinfunction "NRST_7") (pintype "passive"))
    )
    (net (code "55") (name "SWCLK") (class "Default")
      (node (ref "J1") (pin "B8") (pinfunction "SBU2_B8") (pintype "passive"))
      (node (ref "TP3") (pin "1") (pinfunction "1_1") (pintype "passive"))
      (node (ref "U4") (pin "37") (pinfunction "PA14_37") (pintype "passive"))
    )
    (net (code "56") (name "SWDIO") (class "Default")
      (node (ref "J1") (pin "A8") (pinfunction "SBU1_A8") (pintype "passive"))
      (node (ref "TP2") (pin "1") (pinfunction "1_1") (pintype "passive"))
      (node (ref "U4") (pin "34") (pinfunction "PA13_34") (pintype "passive"))
    )
    (net (code "57") (name "VUSB") (class "Default")
      (node (ref "C11") (pin "2") (pinfunction "2_2") (pintype "passive"))
      (node (ref "J1") (pin "A4") (pinfunction "VBUS_A4") (pintype "passive"))
      (node (ref "J1") (pin "A9") (pinfunction "VBUS_A9") (pintype "passive"))
      (node (ref "J1") (pin "B4") (pinfunction "VBUS_B4") (pintype "passive"))
      (node (ref "J1") (pin "B9") (pinfunction "VBUS_B9") (pintype "passive"))
      (node (ref "Q3") (pin "1") (pinfunction "S_1") (pintype "passive"))
      (node (ref "Q3") (pin "2") (pinfunction "S_2") (pintype "passive"))
      (node (ref "Q3") (pin "3") (pinfunction "S_3") (pintype "passive"))
      (node (ref "R16") (pin "1") (pinfunction "1_1") (pintype "passive"))
      (node (ref "R20") (pin "2") (pinfunction "2_2") (pintype "passive"))
      (node (ref "R22") (pin "2") (pinfunction "2_2") (pintype "passive"))
      (node (ref "R4") (pin "2") (pinfunction "2_2") (pintype "passive"))
      (node (ref "U3") (pin "5") (pinfunction "VIN_5") (pintype "input"))
    )
    (net (code "58") (name "unconnected-(J1-RX1+-PadB11)") (class "Default")
      (node (ref "J1") (pin "B11") (pinfunction "RX1+_B11") (pintype "passive"))
    )
    (net (code "59") (name "unconnected-(J1-RX1--PadB10)") (class "Default")
      (node (ref "J1") (pin "B10") (pinfunction "RX1-_B10") (pintype "passive"))
    )
    (net (code "60") (name "unconnected-(J1-RX2+-PadA11)") (class "Default")
      (node (ref "J1") (pin "A11") (pinfunction "RX2+_A11") (pintype "passive"))
    )
    (net (code "61") (name "unconnected-(J1-RX2--PadA10)") (class "Default")
      (node (ref "J1") (pin "A10") (pinfunction "RX2-_A10") (pintype "passive"))
    )
    (net (code "62") (name "unconnected-(J1-TX1+-PadA2)") (class "Default")
      (node (ref "J1") (pin "A2") (pinfunction "TX1+_A2") (pintype "passive"))
    )
    (net (code "63") (name "unconnected-(J1-TX1--PadA3)") (class "Default")
      (node (ref "J1") (pin "A3") (pinfunction "TX1-_A3") (pintype "passive"))
    )
    (net (code "64") (name "unconnected-(J1-TX2+-PadB2)") (class "Default")
      (node (ref "J1") (pin "B2") (pinfunction "TX2+_B2") (pintype "passive"))
    )
    (net (code "65") (name "unconnected-(J1-TX2--PadB3)") (class "Default")
      (node (ref "J1") (pin "B3") (pinfunction "TX2-_B3") (pintype "passive"))
    )
    (net (code "66") (name "unconnected-(LED1-NC-Pad1)") (class "Default")
      (node (ref "LED1") (pin "1") (pinfunction "NC_1") (pintype "passive+no_connect"))
    )
    (net (code "67") (name "unconnected-(LED1-NC-Pad13)") (class "Default")
      (node (ref "LED1") (pin "13") (pinfunction "NC_13") (pintype "passive+no_connect"))
    )
    (net (code "68") (name "unconnected-(LED1-NC-Pad14)") (class "Default")
      (node (ref "LED1") (pin "14") (pinfunction "NC_14") (pintype "passive+no_connect"))
    )
    (net (code "69") (name "unconnected-(LED1-NC-Pad15)") (class "Default")
      (node (ref "LED1") (pin "15") (pinfunction "NC_15") (pintype "passive+no_connect"))
    )
    (net (code "70") (name "unconnected-(LED3-DOUT-Pad1)") (class "Default")
      (node (ref "LED3") (pin "1") (pinfunction "DOUT_1") (pintype "passive"))
    )
    (net (code "71") (name "unconnected-(U2-NC-Pad5)") (class "Default")
      (node (ref "U2") (pin "5") (pinfunction "NC_5") (pintype "passive+no_connect"))
    )
    (net (code "72") (name "unconnected-(U4-PA4-Pad14)") (class "Default")
      (node (ref "U4") (pin "14") (pinfunction "PA4_14") (pintype "passive"))
    )
    (net (code "73") (name "unconnected-(U4-PC13-Pad2)") (class "Default")
      (node (ref "U4") (pin "2") (pinfunction "PC13_2") (pintype "passive+no_connect"))
    )
    (net (code "74") (name "unconnected-(U4-PC14-OSC32_IN-Pad3)") (class "Default")
      (node (ref "U4") (pin "3") (pinfunction "PC14-OSC32_IN_3") (pintype "passive+no_connect"))
    )
    (net (code "75") (name "unconnected-(U4-PC15-OSC32_OUT-Pad4)") (class "Default")
      (node (ref "U4") (pin "4") (pinfunction "PC15-OSC32_OUT_4") (pintype "passive+no_connect"))
    )
  )
)
